# stm32.net
KiCad netlist of a schematic drawn in Altium Designer
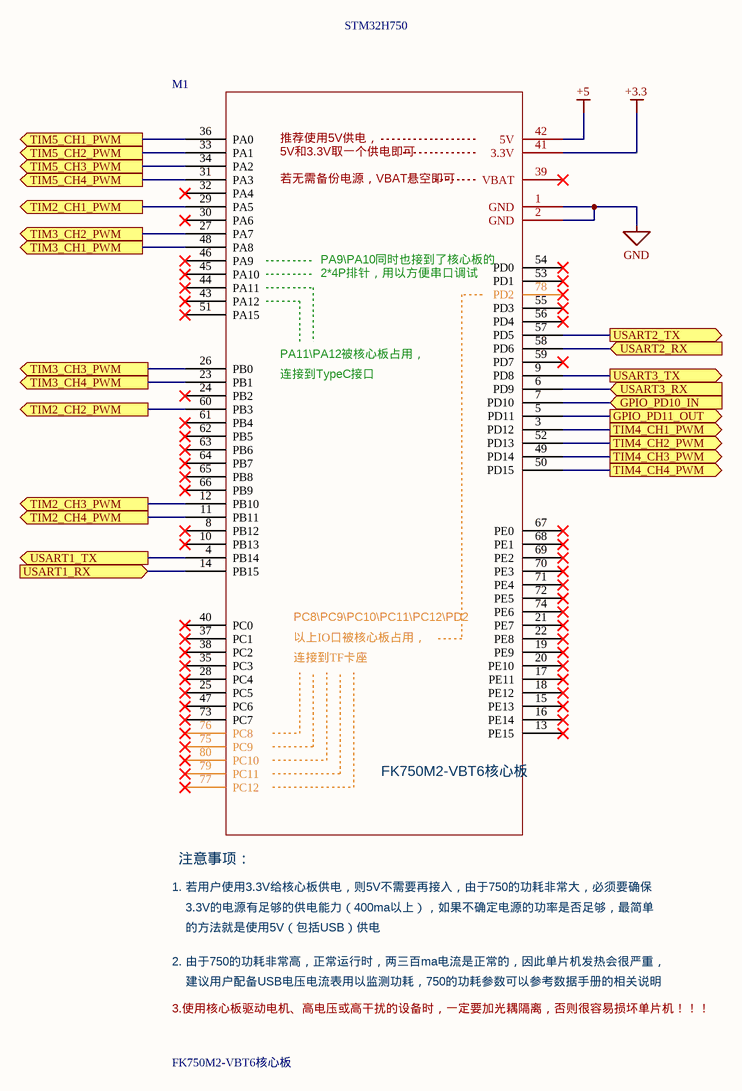
[diagram p0: stm32.SchDoc]

(export (version "E")
  (design (tool "Eeschema 10.0.6"))
  (components
    (comp (ref "M1")
      (value "FK750M2-VBT6核心板")
      (footprint "FK750M2-VBT6(精简版)")
      (libsource (lib "Schlib1") (part "FK750M2-VBT6"))
    )
  )
  (nets
    (net (code "1") (name "+3.3") (class "Default")
      (node (ref "M1") (pin "41") (pinfunction "3.3V_41") (pintype "passive"))
    )
    (net (code "2") (name "+5") (class "Default")
      (node (ref "M1") (pin "42") (pinfunction "5V_42") (pintype "passive"))
    )
    (net (code "3") (name "/GPIO_PD10_IN") (class "Default")
      (node (ref "M1") (pin "7") (pinfunction "PD10_7") (pintype "passive"))
    )
    (net (code "4") (name "/GPIO_PD11_OUT") (class "Default")
      (node (ref "M1") (pin "5") (pinfunction "PD11_5") (pintype "passive"))
    )
    (net (code "5") (name "/TIM2_CH1_PWM") (class "Default")
      (node (ref "M1") (pin "29") (pinfunction "PA5_29") (pintype "passive"))
    )
    (net (code "6") (name "/TIM2_CH2_PWM") (class "Default")
      (node (ref "M1") (pin "60") (pinfunction "PB3_60") (pintype "passive"))
    )
    (net (code "7") (name "/TIM2_CH3_PWM") (class "Default")
      (node (ref "M1") (pin "12") (pinfunction "PB10_12") (pintype "passive"))
    )
    (net (code "8") (name "/TIM2_CH4_PWM") (class "Default")
      (node (ref "M1") (pin "11") (pinfunction "PB11_11") (pintype "passive"))
    )
    (net (code "9") (name "/TIM3_CH1_PWM") (class "Default")
      (node (ref "M1") (pin "48") (pinfunction "PA8_48") (pintype "passive"))
    )
    (net (code "10") (name "/TIM3_CH2_PWM") (class "Default")
      (node (ref "M1") (pin "27") (pinfunction "PA7_27") (pintype "passive"))
    )
    (net (code "11") (name "/TIM3_CH3_PWM") (class "Default")
      (node (ref "M1") (pin "26") (pinfunction "PB0_26") (pintype "passive"))
    )
    (net (code "12") (name "/TIM3_CH4_PWM") (class "Default")
      (node (ref "M1") (pin "23") (pinfunction "PB1_23") (pintype "passive"))
    )
    (net (code "13") (name "/TIM4_CH1_PWM") (class "Default")
      (node (ref "M1") (pin "3") (pinfunction "PD12_3") (pintype "passive"))
    )
    (net (code "14") (name "/TIM4_CH2_PWM") (class "Default")
      (node (ref "M1") (pin "52") (pinfunction "PD13_52") (pintype "passive"))
    )
    (net (code "15") (name "/TIM4_CH3_PWM") (class "Default")
      (node (ref "M1") (pin "49") (pinfunction "PD14_49") (pintype "passive"))
    )
    (net (code "16") (name "/TIM4_CH4_PWM") (class "Default")
      (node (ref "M1") (pin "50") (pinfunction "PD15_50") (pintype "passive"))
    )
    (net (code "17") (name "/TIM5_CH1_PWM") (class "Default")
      (node (ref "M1") (pin "36") (pinfunction "PA0_36") (pintype "passive"))
    )
    (net (code "18") (name "/TIM5_CH2_PWM") (class "Default")
      (node (ref "M1") (pin "33") (pinfunction "PA1_33") (pintype "passive"))
    )
    (net (code "19") (name "/TIM5_CH3_PWM") (class "Default")
      (node (ref "M1") (pin "34") (pinfunction "PA2_34") (pintype "passive"))
    )
    (net (code "20") (name "/TIM5_CH4_PWM") (class "Default")
      (node (ref "M1") (pin "31") (pinfunction "PA3_31") (pintype "passive"))
    )
    (net (code "21") (name "/USART1_RX") (class "Default")
      (node (ref "M1") (pin "14") (pinfunction "PB15_14") (pintype "passive"))
    )
    (net (code "22") (name "/USART1_TX") (class "Default")
      (node (ref "M1") (pin "4") (pinfunction "PB14_4") (pintype "passive"))
    )
    (net (code "23") (name "/USART2_RX") (class "Default")
      (node (ref "M1") (pin "58") (pinfunction "PD6_58") (pintype "passive"))
    )
    (net (code "24") (name "/USART2_TX") (class "Default")
      (node (ref "M1") (pin "57") (pinfunction "PD5_57") (pintype "passive"))
    )
    (net (code "25") (name "/USART3_RX") (class "Default")
      (node (ref "M1") (pin "6") (pinfunction "PD9_6") (pintype "passive"))
    )
    (net (code "26") (name "/USART3_TX") (class "Default")
      (node (ref "M1") (pin "9") (pinfunction "PD8_9") (pintype "passive"))
    )
    (net (code "27") (name "GND") (class "Default")
      (node (ref "M1") (pin "1") (pinfunction "GND_1") (pintype "passive"))
      (node (ref "M1") (pin "2") (pinfunction "GND_2") (pintype "passive"))
    )
    (net (code "28") (name "unconnected-(M1-PA4-Pad32)") (class "Default")
      (node (ref "M1") (pin "32") (pinfunction "PA4_32") (pintype "passive+no_connect"))
    )
    (net (code "29") (name "unconnected-(M1-PA6-Pad30)") (class "Default")
      (node (ref "M1") (pin "30") (pinfunction "PA6_30") (pintype "passive+no_connect"))
    )
    (net (code "30") (name "unconnected-(M1-PA9-Pad46)") (class "Default")
      (node (ref "M1") (pin "46") (pinfunction "PA9_46") (pintype "passive+no_connect"))
    )
    (net (code "31") (name "unconnected-(M1-PA10-Pad45)") (class "Default")
      (node (ref "M1") (pin "45") (pinfunction "PA10_45") (pintype "passive+no_connect"))
    )
    (net (code "32") (name "unconnected-(M1-PA11-Pad44)") (class "Default")
      (node (ref "M1") (pin "44") (pinfunction "PA11_44") (pintype "passive+no_connect"))
    )
    (net (code "33") (name "unconnected-(M1-PA12-Pad43)") (class "Default")
      (node (ref "M1") (pin "43") (pinfunction "PA12_43") (pintype "passive+no_connect"))
    )
    (net (code "34") (name "unconnected-(M1-PA15-Pad51)") (class "Default")
      (node (ref "M1") (pin "51") (pinfunction "PA15_51") (pintype "passive+no_connect"))
    )
    (net (code "35") (name "unconnected-(M1-PB2-Pad24)") (class "Default")
      (node (ref "M1") (pin "24") (pinfunction "PB2_24") (pintype "passive+no_connect"))
    )
    (net (code "36") (name "unconnected-(M1-PB4-Pad61)") (class "Default")
      (node (ref "M1") (pin "61") (pinfunction "PB4_61") (pintype "passive+no_connect"))
    )
    (net (code "37") (name "unconnected-(M1-PB5-Pad62)") (class "Default")
      (node (ref "M1") (pin "62") (pinfunction "PB5_62") (pintype "passive+no_connect"))
    )
    (net (code "38") (name "unconnected-(M1-PB6-Pad63)") (class "Default")
      (node (ref "M1") (pin "63") (pinfunction "PB6_63") (pintype "passive+no_connect"))
    )
    (net (code "39") (name "unconnected-(M1-PB7-Pad64)") (class "Default")
      (node (ref "M1") (pin "64") (pinfunction "PB7_64") (pintype "passive+no_connect"))
    )
    (net (code "40") (name "unconnected-(M1-PB8-Pad65)") (class "Default")
      (node (ref "M1") (pin "65") (pinfunction "PB8_65") (pintype "passive+no_connect"))
    )
    (net (code "41") (name "unconnected-(M1-PB9-Pad66)") (class "Default")
      (node (ref "M1") (pin "66") (pinfunction "PB9_66") (pintype "passive+no_connect"))
    )
    (net (code "42") (name "unconnected-(M1-PB12-Pad8)") (class "Default")
      (node (ref "M1") (pin "8") (pinfunction "PB12_8") (pintype "passive+no_connect"))
    )
    (net (code "43") (name "unconnected-(M1-PB13-Pad10)") (class "Default")
      (node (ref "M1") (pin "10") (pinfunction "PB13_10") (pintype "passive+no_connect"))
    )
    (net (code "44") (name "unconnected-(M1-PC0-Pad40)") (class "Default")
      (node (ref "M1") (pin "40") (pinfunction "PC0_40") (pintype "passive+no_connect"))
    )
    (net (code "45") (name "unconnected-(M1-PC1-Pad37)") (class "Default")
      (node (ref "M1") (pin "37") (pinfunction "PC1_37") (pintype "passive+no_connect"))
    )
    (net (code "46") (name "unconnected-(M1-PC2-Pad38)") (class "Default")
      (node (ref "M1") (pin "38") (pinfunction "PC2_38") (pintype "passive+no_connect"))
    )
    (net (code "47") (name "unconnected-(M1-PC3-Pad35)") (class "Default")
      (node (ref "M1") (pin "35") (pinfunction "PC3_35") (pintype "passive+no_connect"))
    )
    (net (code "48") (name "unconnected-(M1-PC4-Pad28)") (class "Default")
      (node (ref "M1") (pin "28") (pinfunction "PC4_28") (pintype "passive+no_connect"))
    )
    (net (code "49") (name "unconnected-(M1-PC5-Pad25)") (class "Default")
      (node (ref "M1") (pin "25") (pinfunction "PC5_25") (pintype "passive+no_connect"))
    )
    (net (code "50") (name "unconnected-(M1-PC6-Pad47)") (class "Default")
      (node (ref "M1") (pin "47") (pinfunction "PC6_47") (pintype "passive+no_connect"))
    )
    (net (code "51") (name "unconnected-(M1-PC7-Pad73)") (class "Default")
      (node (ref "M1") (pin "73") (pinfunction "PC7_73") (pintype "passive+no_connect"))
    )
    (net (code "52") (name "unconnected-(M1-PC8-Pad76)") (class "Default")
      (node (ref "M1") (pin "76") (pinfunction "PC8_76") (pintype "passive+no_connect"))
    )
    (net (code "53") (name "unconnected-(M1-PC9-Pad75)") (class "Default")
      (node (ref "M1") (pin "75") (pinfunction "PC9_75") (pintype "passive+no_connect"))
    )
    (net (code "54") (name "unconnected-(M1-PC10-Pad80)") (class "Default")
      (node (ref "M1") (pin "80") (pinfunction "PC10_80") (pintype "passive+no_connect"))
    )
    (net (code "55") (name "unconnected-(M1-PC11-Pad79)") (class "Default")
      (node (ref "M1") (pin "79") (pinfunction "PC11_79") (pintype "passive+no_connect"))
    )
    (net (code "56") (name "unconnected-(M1-PC12-Pad77)") (class "Default")
      (node (ref "M1") (pin "77") (pinfunction "PC12_77") (pintype "passive+no_connect"))
    )
    (net (code "57") (name "unconnected-(M1-PD0-Pad54)") (class "Default")
      (node (ref "M1") (pin "54") (pinfunction "PD0_54") (pintype "passive+no_connect"))
    )
    (net (code "58") (name "unconnected-(M1-PD1-Pad53)") (class "Default")
      (node (ref "M1") (pin "53") (pinfunction "PD1_53") (pintype "passive+no_connect"))
    )
    (net (code "59") (name "unconnected-(M1-PD2-Pad78)") (class "Default")
      (node (ref "M1") (pin "78") (pinfunction "PD2_78") (pintype "passive+no_connect"))
    )
    (net (code "60") (name "unconnected-(M1-PD3-Pad55)") (class "Default")
      (node (ref "M1") (pin "55") (pinfunction "PD3_55") (pintype "passive+no_connect"))
    )
    (net (code "61") (name "unconnected-(M1-PD4-Pad56)") (class "Default")
      (node (ref "M1") (pin "56") (pinfunction "PD4_56") (pintype "passive+no_connect"))
    )
    (net (code "62") (name "unconnected-(M1-PD7-Pad59)") (class "Default")
      (node (ref "M1") (pin "59") (pinfunction "PD7_59") (pintype "passive+no_connect"))
    )
    (net (code "63") (name "unconnected-(M1-PE0-Pad67)") (class "Default")
      (node (ref "M1") (pin "67") (pinfunction "PE0_67") (pintype "passive+no_connect"))
    )
    (net (code "64") (name "unconnected-(M1-PE1-Pad68)") (class "Default")
      (node (ref "M1") (pin "68") (pinfunction "PE1_68") (pintype "passive+no_connect"))
    )
    (net (code "65") (name "unconnected-(M1-PE2-Pad69)") (class "Default")
      (node (ref "M1") (pin "69") (pinfunction "PE2_69") (pintype "passive+no_connect"))
    )
    (net (code "66") (name "unconnected-(M1-PE3-Pad70)") (class "Default")
      (node (ref "M1") (pin "70") (pinfunction "PE3_70") (pintype "passive+no_connect"))
    )
    (net (code "67") (name "unconnected-(M1-PE4-Pad71)") (class "Default")
      (node (ref "M1") (pin "71") (pinfunction "PE4_71") (pintype "passive+no_connect"))
    )
    (net (code "68") (name "unconnected-(M1-PE5-Pad72)") (class "Default")
      (node (ref "M1") (pin "72") (pinfunction "PE5_72") (pintype "passive+no_connect"))
    )
    (net (code "69") (name "unconnected-(M1-PE6-Pad74)") (class "Default")
      (node (ref "M1") (pin "74") (pinfunction "PE6_74") (pintype "passive+no_connect"))
    )
    (net (code "70") (name "unconnected-(M1-PE7-Pad21)") (class "Default")
      (node (ref "M1") (pin "21") (pinfunction "PE7_21") (pintype "passive+no_connect"))
    )
    (net (code "71") (name "unconnected-(M1-PE8-Pad22)") (class "Default")
      (node (ref "M1") (pin "22") (pinfunction "PE8_22") (pintype "passive+no_connect"))
    )
    (net (code "72") (name "unconnected-(M1-PE9-Pad19)") (class "Default")
      (node (ref "M1") (pin "19") (pinfunction "PE9_19") (pintype "passive+no_connect"))
    )
    (net (code "73") (name "unconnected-(M1-PE10-Pad20)") (class "Default")
      (node (ref "M1") (pin "20") (pinfunction "PE10_20") (pintype "passive+no_connect"))
    )
    (net (code "74") (name "unconnected-(M1-PE11-Pad17)") (class "Default")
      (node (ref "M1") (pin "17") (pinfunction "PE11_17") (pintype "passive+no_connect"))
    )
    (net (code "75") (name "unconnected-(M1-PE12-Pad18)") (class "Default")
      (node (ref "M1") (pin "18") (pinfunction "PE12_18") (pintype "passive+no_connect"))
    )
    (net (code "76") (name "unconnected-(M1-PE13-Pad15)") (class "Default")
      (node (ref "M1") (pin "15") (pinfunction "PE13_15") (pintype "passive+no_connect"))
    )
    (net (code "77") (name "unconnected-(M1-PE14-Pad16)") (class "Default")
      (node (ref "M1") (pin "16") (pinfunction "PE14_16") (pintype "passive+no_connect"))
    )
    (net (code "78") (name "unconnected-(M1-PE15-Pad13)") (class "Default")
      (node (ref "M1") (pin "13") (pinfunction "PE15_13") (pintype "passive+no_connect"))
    )
    (net (code "79") (name "unconnected-(M1-VBAT-Pad39)") (class "Default")
      (node (ref "M1") (pin "39") (pinfunction "VBAT_39") (pintype "passive+no_connect"))
    )
  )
)
